# TSOC_ESP32S.net
KiCad netlist of a schematic drawn in EAGLE
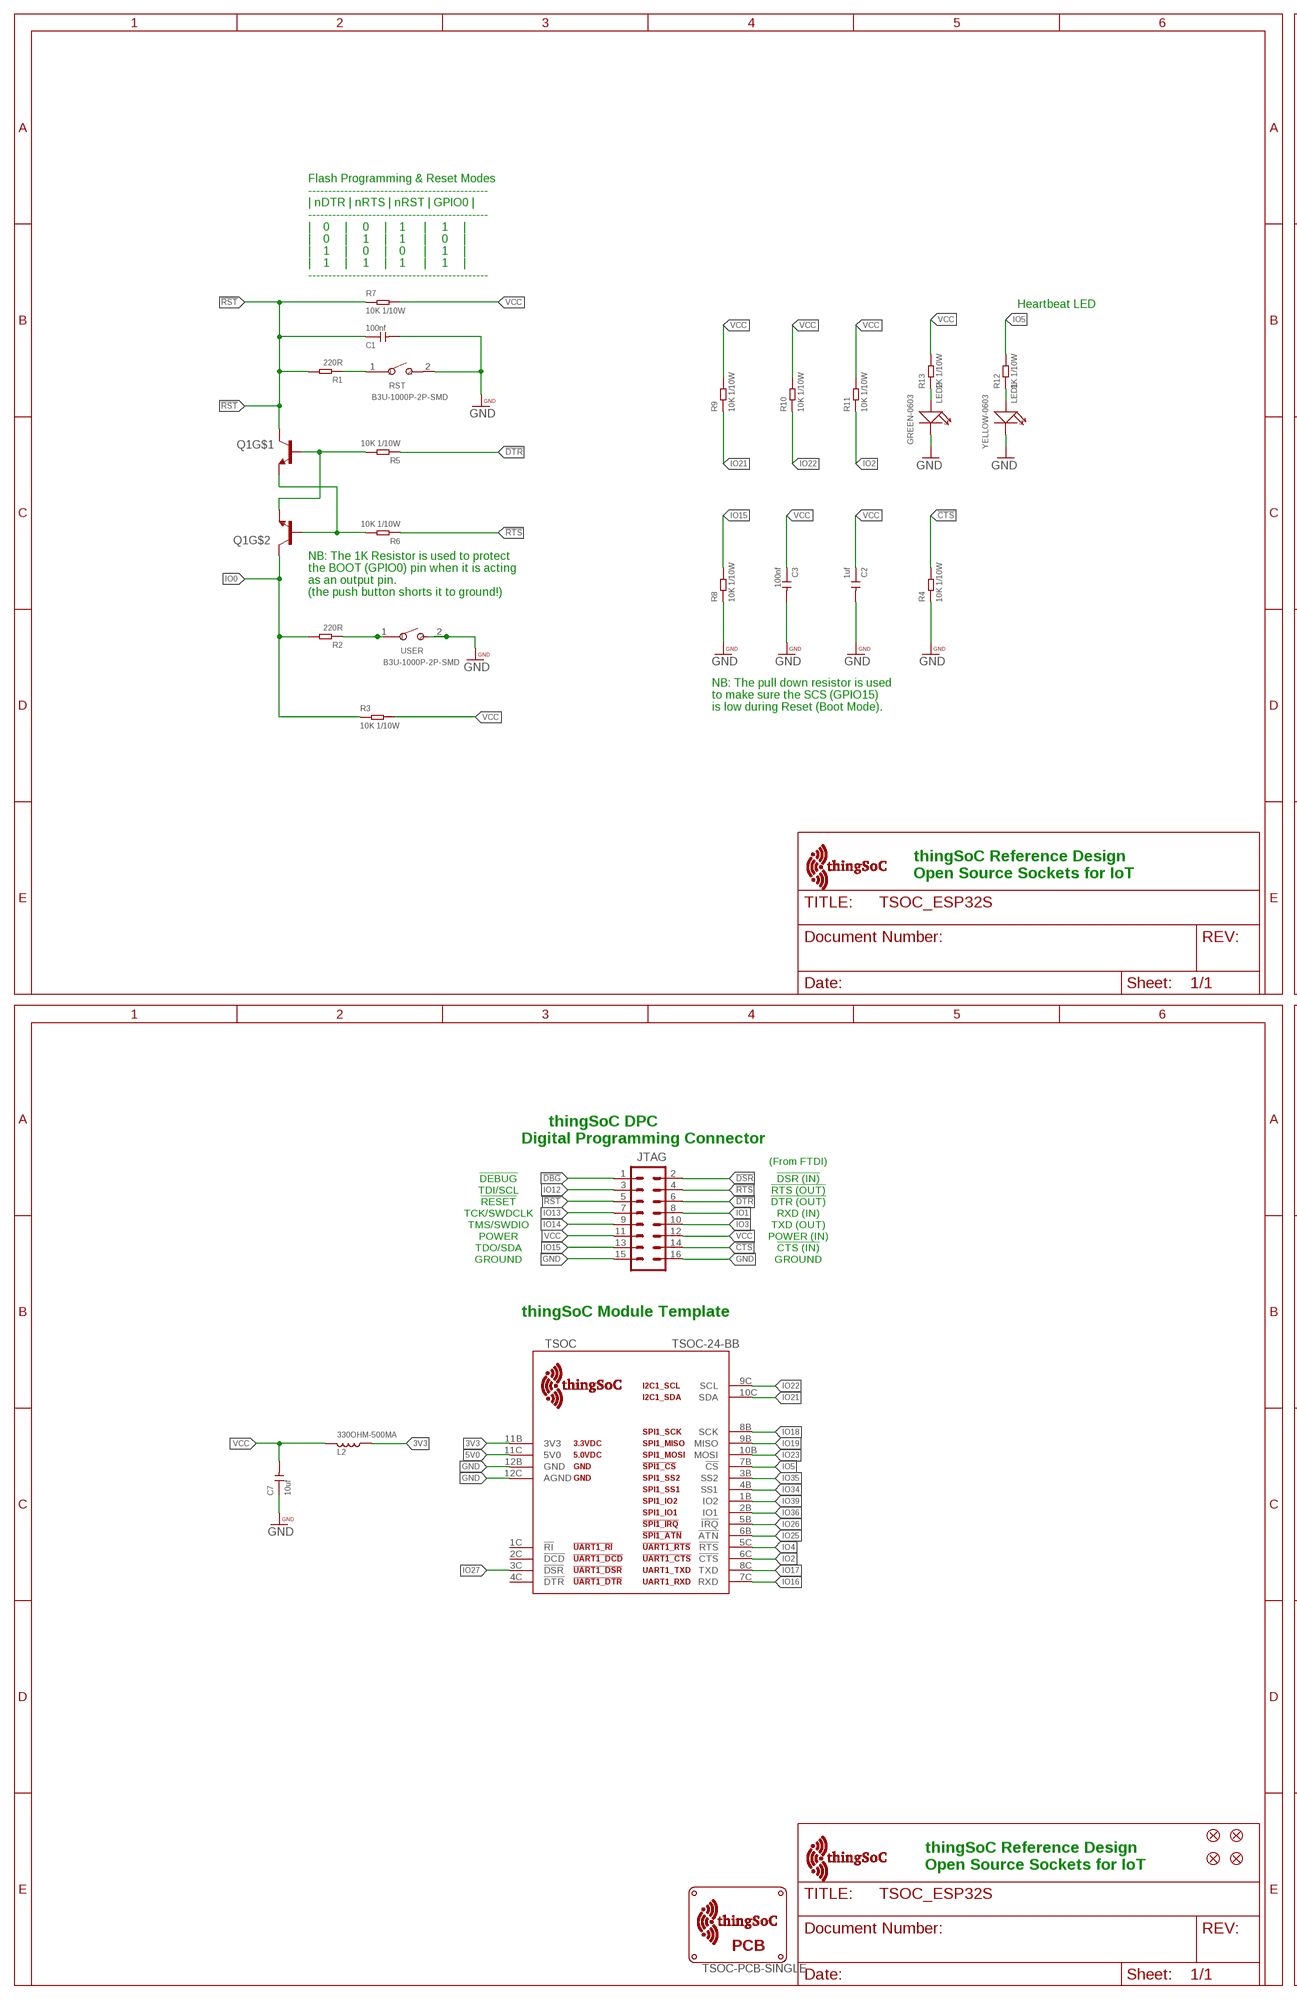
[diagram p0: schematic, sheet 1, part 1 of 2]
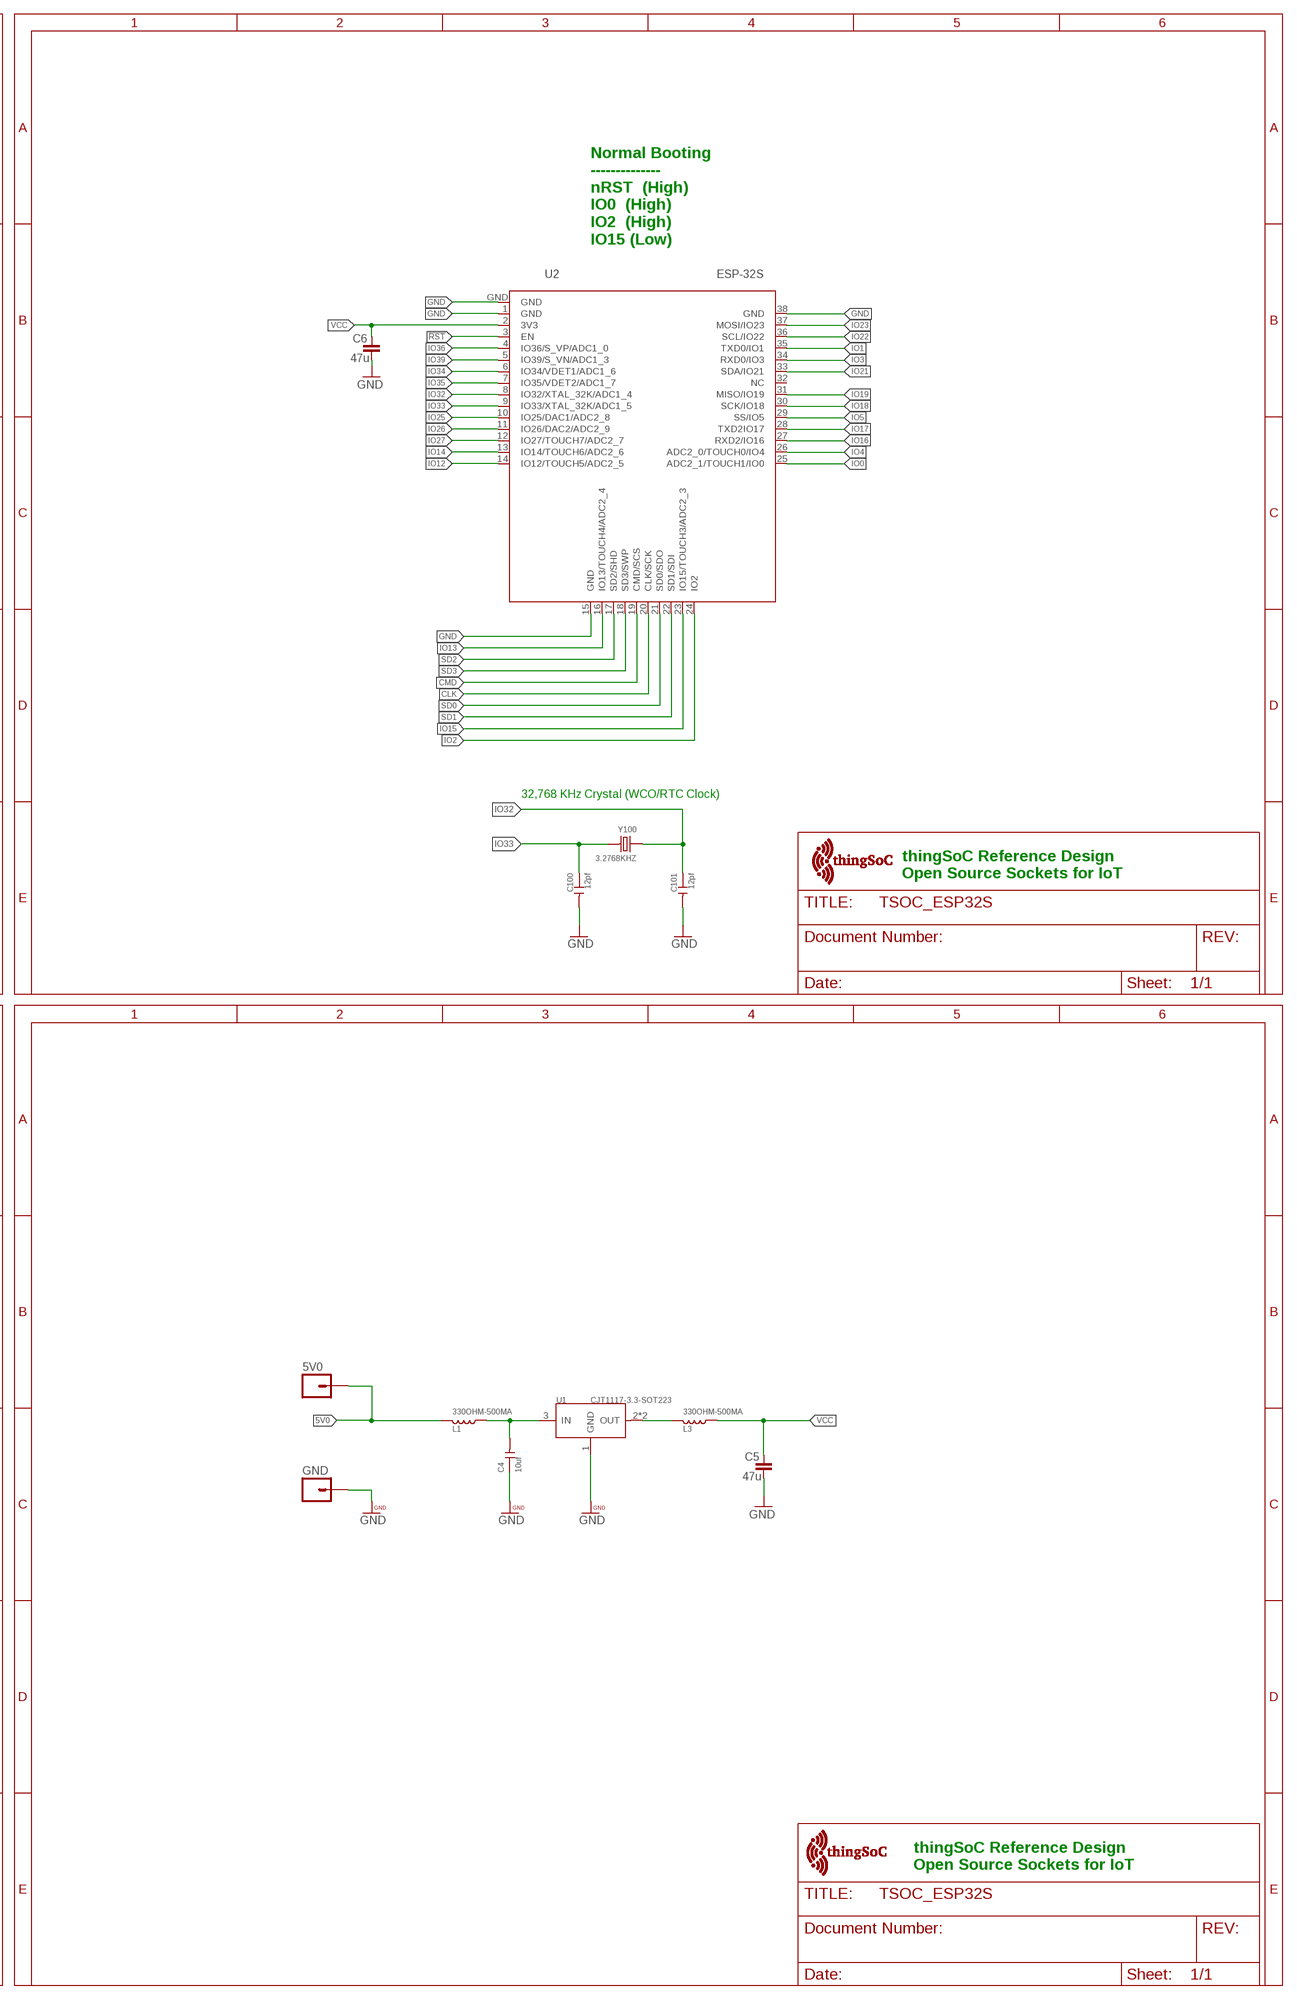
[diagram p1: schematic, sheet 1, part 2 of 2]

(export (version "E")
  (design (tool "Eeschema 10.0.6"))
  (components
    (comp (ref "$$U$1")
      (value "TSOC-LOGO-SMALL")
      (footprint "eagle-import:TSOC-LOGO-SML")
      (libsource (lib "eagle-import") (part "TSOC-LOGO-SMALL"))
    )
    (comp (ref "$$U$2")
      (value "TSOC-LOGO-SMALL")
      (footprint "eagle-import:TSOC-LOGO-SML")
      (libsource (lib "eagle-import") (part "TSOC-LOGO-SMALL"))
    )
    (comp (ref "5V0")
      (value "M01PTH")
      (footprint "eagle-import:1X01")
      (libsource (lib "eagle-import") (part "M01PTH"))
    )
    (comp (ref "C1")
      (value "100nf")
      (footprint "eagle-import:C0603")
      (fields (field (name "MPN") "CC0603KRX7R9BB104"))
      (libsource (lib "eagle-import") (part "CERAMIC-100NF-50V-10%-X7R(0603)"))
    )
    (comp (ref "C2")
      (value "1uf")
      (footprint "eagle-import:C0603")
      (fields (field (name "MPN") "CC0603KRX7R8BB105"))
      (libsource (lib "eagle-import") (part "CERAMIC-1UF-25V-10%-X7R(0603)"))
    )
    (comp (ref "C3")
      (value "100nf")
      (footprint "eagle-import:C0603")
      (fields (field (name "MPN") "CC0603KRX7R9BB104"))
      (libsource (lib "eagle-import") (part "CERAMIC-100NF-50V-10%-X7R(0603)"))
    )
    (comp (ref "C4")
      (value "10uf")
      (footprint "eagle-import:C0603")
      (fields (field (name "MPN") "CC0603KRX5R6BB106"))
      (libsource (lib "eagle-import") (part "CERAMIC-10UF-10V-10%-X5R(0603)"))
    )
    (comp (ref "C5")
      (value "47u")
      (footprint "eagle-import:C1206")
      (libsource (lib "eagle-import") (part "CAPACITOR-1206"))
    )
    (comp (ref "C6")
      (value "47u")
      (footprint "eagle-import:C1206")
      (libsource (lib "eagle-import") (part "CAPACITOR-1206"))
    )
    (comp (ref "C7")
      (value "10uf")
      (footprint "eagle-import:C0603")
      (fields (field (name "MPN") "CC0603KRX5R6BB106"))
      (libsource (lib "eagle-import") (part "CERAMIC-10UF-10V-10%-X5R(0603)"))
    )
    (comp (ref "C100")
      (value "12pf")
      (footprint "eagle-import:C0603")
      (fields (field (name "MPN") "CC0603JRNPO9BN120"))
      (libsource (lib "eagle-import") (part "CERAMIC-12PF-50V-5%-NPO(0603)"))
    )
    (comp (ref "C101")
      (value "12pf")
      (footprint "eagle-import:C0603")
      (fields (field (name "MPN") "CC0603JRNPO9BN120"))
      (libsource (lib "eagle-import") (part "CERAMIC-12PF-50V-5%-NPO(0603)"))
    )
    (comp (ref "FID1")
      (value "FIDUCIALUFIDUCIAL")
      (footprint "eagle-import:MICRO-FIDUCIAL")
      (libsource (lib "eagle-import") (part "FIDUCIALUFIDUCIAL"))
    )
    (comp (ref "FID2")
      (value "FIDUCIALUFIDUCIAL")
      (footprint "eagle-import:MICRO-FIDUCIAL")
      (libsource (lib "eagle-import") (part "FIDUCIALUFIDUCIAL"))
    )
    (comp (ref "FID3")
      (value "FIDUCIALUFIDUCIAL")
      (footprint "eagle-import:MICRO-FIDUCIAL")
      (libsource (lib "eagle-import") (part "FIDUCIALUFIDUCIAL"))
    )
    (comp (ref "FID4")
      (value "FIDUCIALUFIDUCIAL")
      (footprint "eagle-import:MICRO-FIDUCIAL")
      (libsource (lib "eagle-import") (part "FIDUCIALUFIDUCIAL"))
    )
    (comp (ref "GND")
      (value "M01PTH")
      (footprint "eagle-import:1X01")
      (libsource (lib "eagle-import") (part "M01PTH"))
    )
    (comp (ref "JTAG")
      (value "M08X2")
      (footprint "eagle-import:2X8")
      (libsource (lib "eagle-import") (part "M08X2"))
    )
    (comp (ref "L1")
      (value "330OHM-500MA")
      (footprint "eagle-import:L0603")
      (fields (field (name "MPN") "BLM18AG121SN1D"))
      (libsource (lib "eagle-import") (part "SMD-FERRITE-CHIP-120-OHM-500MA(0603)"))
    )
    (comp (ref "L2")
      (value "330OHM-500MA")
      (footprint "eagle-import:L0603")
      (fields (field (name "MPN") "BLM18AG121SN1D"))
      (libsource (lib "eagle-import") (part "SMD-FERRITE-CHIP-120-OHM-500MA(0603)"))
    )
    (comp (ref "L3")
      (value "330OHM-500MA")
      (footprint "eagle-import:L0603")
      (fields (field (name "MPN") "BLM18AG121SN1D"))
      (libsource (lib "eagle-import") (part "SMD-FERRITE-CHIP-120-OHM-500MA(0603)"))
    )
    (comp (ref "LED1")
      (value "YELLOW-0603")
      (footprint "eagle-import:LED-0603")
      (fields (field (name "MPN") "19-217-Y5C-AM1N1VY-3T"))
      (libsource (lib "eagle-import") (part "SMD-LED-CLEAR-YELLOW(0603)"))
    )
    (comp (ref "LED2")
      (value "GREEN-0603")
      (footprint "eagle-import:LED-0603")
      (fields (field (name "MPN") "19-217-G7C-AN1P2-3T"))
      (libsource (lib "eagle-import") (part "SMD-LED-CLEAR-GREEN(0603)"))
    )
    (comp (ref "Q1")
      (value "MMBT2222A")
      (footprint "eagle-import:SOT363")
      (libsource (lib "eagle-import") (part "MMDT3904"))
    )
    (comp (ref "R1")
      (value "220R")
      (footprint "eagle-import:R0603")
      (fields (field (name "MPN") "RC0603JR-07220RL"))
      (libsource (lib "eagle-import") (part "SMD-RES-220R-5%-1/10W(0603)"))
    )
    (comp (ref "R2")
      (value "220R")
      (footprint "eagle-import:R0603")
      (fields (field (name "MPN") "RC0603JR-07220RL"))
      (libsource (lib "eagle-import") (part "SMD-RES-220R-5%-1/10W(0603)"))
    )
    (comp (ref "R3")
      (value "10K 1/10W")
      (footprint "eagle-import:R0603")
      (fields (field (name "MPN") "RC0603JR-0710KL"))
      (libsource (lib "eagle-import") (part "SMD-RES-10K-5%-1/10W(0603)"))
    )
    (comp (ref "R4")
      (value "10K 1/10W")
      (footprint "eagle-import:R0603")
      (fields (field (name "MPN") "RC0603JR-0710KL"))
      (libsource (lib "eagle-import") (part "SMD-RES-10K-5%-1/10W(0603)"))
    )
    (comp (ref "R5")
      (value "10K 1/10W")
      (footprint "eagle-import:R0603")
      (fields (field (name "MPN") "RC0603JR-0710KL"))
      (libsource (lib "eagle-import") (part "SMD-RES-10K-5%-1/10W(0603)"))
    )
    (comp (ref "R6")
      (value "10K 1/10W")
      (footprint "eagle-import:R0603")
      (fields (field (name "MPN") "RC0603JR-0710KL"))
      (libsource (lib "eagle-import") (part "SMD-RES-10K-5%-1/10W(0603)"))
    )
    (comp (ref "R7")
      (value "10K 1/10W")
      (footprint "eagle-import:R0603")
      (fields (field (name "MPN") "RC0603JR-0710KL"))
      (libsource (lib "eagle-import") (part "SMD-RES-10K-5%-1/10W(0603)"))
    )
    (comp (ref "R8")
      (value "10K 1/10W")
      (footprint "eagle-import:R0603")
      (fields (field (name "MPN") "RC0603JR-0710KL"))
      (libsource (lib "eagle-import") (part "SMD-RES-10K-5%-1/10W(0603)"))
    )
    (comp (ref "R9")
      (value "10K 1/10W")
      (footprint "eagle-import:R0603")
      (fields (field (name "MPN") "RC0603JR-0710KL"))
      (libsource (lib "eagle-import") (part "SMD-RES-10K-5%-1/10W(0603)"))
    )
    (comp (ref "R10")
      (value "10K 1/10W")
      (footprint "eagle-import:R0603")
      (fields (field (name "MPN") "RC0603JR-0710KL"))
      (libsource (lib "eagle-import") (part "SMD-RES-10K-5%-1/10W(0603)"))
    )
    (comp (ref "R11")
      (value "10K 1/10W")
      (footprint "eagle-import:R0603")
      (fields (field (name "MPN") "RC0603JR-0710KL"))
      (libsource (lib "eagle-import") (part "SMD-RES-10K-5%-1/10W(0603)"))
    )
    (comp (ref "R12")
      (value "1K 1/10W")
      (footprint "eagle-import:R0603")
      (fields (field (name "MPN") "RC0603JR-071KL"))
      (libsource (lib "eagle-import") (part "SMD-RES-1K-5%-1/10W(0603)"))
    )
    (comp (ref "R13")
      (value "1K 1/10W")
      (footprint "eagle-import:R0603")
      (fields (field (name "MPN") "RC0603JR-071KL"))
      (libsource (lib "eagle-import") (part "SMD-RES-1K-5%-1/10W(0603)"))
    )
    (comp (ref "RST")
      (value "B3U-1000P-2P-SMD")
      (footprint "eagle-import:SW2-2.6-3.0X2.5X1.2+0.4MM")
      (libsource (lib "eagle-import") (part "SMD-BUTTON(2P-3.0X2.5X1.2+0.4MM)-B3U-1000P-2P-SMD"))
    )
    (comp (ref "TSOC")
      (value "TSOC-24-BB")
      (footprint "eagle-import:TSOC-BB-S24")
      (libsource (lib "eagle-import") (part "TSOC-24-BB"))
    )
    (comp (ref "U$1")
      (value "TSOC-PCB-SINGLE")
      (footprint "eagle-import:TSOC-BB-BRD-DIM")
      (libsource (lib "eagle-import") (part "TSOC-PCB-SINGLE"))
    )
    (comp (ref "U$101")
      (value "TSOC-LOGO-SMALL")
      (footprint "eagle-import:TSOC-LOGO-SML")
      (libsource (lib "eagle-import") (part "TSOC-LOGO-SMALL"))
    )
    (comp (ref "U$102")
      (value "TSOC-LOGO-LRG")
      (footprint "eagle-import:TSOC-LOGO-LRG")
      (libsource (lib "eagle-import") (part "TSOC-LOGO-LRG"))
    )
    (comp (ref "U1")
      (value "CJT1117-3.3-SOT223")
      (footprint "eagle-import:SOT-223")
      (fields (field (name "MPN") "CJT1117-3.3"))
      (libsource (lib "eagle-import") (part "PMIC-CJT1117-3.3(SOT223)"))
    )
    (comp (ref "U2")
      (value "ESP-32S")
      (footprint "eagle-import:ESP-32S")
      (libsource (lib "eagle-import") (part "ESP-32S"))
    )
    (comp (ref "USER")
      (value "B3U-1000P-2P-SMD")
      (footprint "eagle-import:SW2-2.6-3.0X2.5X1.2+0.4MM")
      (libsource (lib "eagle-import") (part "SMD-BUTTON(2P-3.0X2.5X1.2+0.4MM)-B3U-1000P-2P-SMD"))
    )
    (comp (ref "Y100")
      (value "3.2768KHZ")
      (footprint "eagle-import:X2-SMD-L2.0X1.2X0.55MM")
      (fields (field (name "MPN") "FC-12M"))
      (libsource (lib "eagle-import") (part "SMD-CRYSTAL-32.768KHZ-12.5PF-20PPM-90K(2P-L2.0X1.2MM)"))
    )
  )
  (nets
    (net (code "1") (name "/~{CTS}") (class "Default")
      (node (ref "JTAG") (pin "14") (pinfunction "14_14") (pintype "passive"))
      (node (ref "R4") (pin "2") (pinfunction "2_2") (pintype "passive"))
    )
    (net (code "2") (name "/~{DBG}") (class "Default")
      (node (ref "JTAG") (pin "1") (pinfunction "1_1") (pintype "passive"))
    )
    (net (code "3") (name "/~{DSR}") (class "Default")
      (node (ref "JTAG") (pin "2") (pinfunction "2_2") (pintype "passive"))
    )
    (net (code "4") (name "/~{DTR}") (class "Default")
      (node (ref "JTAG") (pin "6") (pinfunction "6_6") (pintype "passive"))
      (node (ref "R5") (pin "1") (pinfunction "1_1") (pintype "passive"))
    )
    (net (code "5") (name "/~{RST}") (class "Default")
      (node (ref "C1") (pin "1") (pinfunction "1_1") (pintype "passive"))
      (node (ref "JTAG") (pin "5") (pinfunction "5_5") (pintype "passive"))
      (node (ref "Q1") (pin "3") (pinfunction "C_3") (pintype "passive"))
      (node (ref "R1") (pin "2") (pinfunction "2_2") (pintype "passive"))
      (node (ref "R7") (pin "1") (pinfunction "1_1") (pintype "passive"))
      (node (ref "U2") (pin "3") (pinfunction "EN_3") (pintype "bidirectional"))
    )
    (net (code "6") (name "/~{RTS}") (class "Default")
      (node (ref "JTAG") (pin "4") (pinfunction "4_4") (pintype "passive"))
      (node (ref "R6") (pin "1") (pinfunction "1_1") (pintype "passive"))
    )
    (net (code "7") (name "3V3") (class "Default")
      (node (ref "L2") (pin "2") (pinfunction "2_2") (pintype "passive"))
      (node (ref "TSOC") (pin "11B") (pinfunction "3V3_11B") (pintype "bidirectional"))
    )
    (net (code "8") (name "5V0") (class "Default")
      (node (ref "5V0") (pin "1") (pinfunction "1_1") (pintype "passive"))
      (node (ref "L1") (pin "1") (pinfunction "1_1") (pintype "passive"))
      (node (ref "TSOC") (pin "11C") (pinfunction "5V0_11C") (pintype "bidirectional"))
    )
    (net (code "9") (name "CLK") (class "Default")
      (node (ref "U2") (pin "20") (pinfunction "CLK/SCK_20") (pintype "bidirectional"))
    )
    (net (code "10") (name "CMD") (class "Default")
      (node (ref "U2") (pin "19") (pinfunction "CMD/SCS_19") (pintype "bidirectional"))
    )
    (net (code "11") (name "GND") (class "Default")
      (node (ref "C1") (pin "2") (pinfunction "2_2") (pintype "passive"))
      (node (ref "C100") (pin "2") (pinfunction "2_2") (pintype "passive"))
      (node (ref "C101") (pin "2") (pinfunction "2_2") (pintype "passive"))
      (node (ref "C2") (pin "2") (pinfunction "2_2") (pintype "passive"))
      (node (ref "C3") (pin "2") (pinfunction "2_2") (pintype "passive"))
      (node (ref "C4") (pin "1") (pinfunction "1_1") (pintype "passive"))
      (node (ref "C5") (pin "1") (pinfunction "1_1") (pintype "passive"))
      (node (ref "C6") (pin "1") (pinfunction "1_1") (pintype "passive"))
      (node (ref "C7") (pin "1") (pinfunction "1_1") (pintype "passive"))
      (node (ref "GND") (pin "1") (pinfunction "1_1") (pintype "passive"))
      (node (ref "JTAG") (pin "15") (pinfunction "15_15") (pintype "passive"))
      (node (ref "JTAG") (pin "16") (pinfunction "16_16") (pintype "passive"))
      (node (ref "LED1") (pin "-") (pinfunction "-_-") (pintype "passive"))
      (node (ref "LED2") (pin "-") (pinfunction "-_-") (pintype "passive"))
      (node (ref "R4") (pin "1") (pinfunction "1_1") (pintype "passive"))
      (node (ref "R8") (pin "1") (pinfunction "1_1") (pintype "passive"))
      (node (ref "RST") (pin "2") (pinfunction "2_2") (pintype "bidirectional"))
      (node (ref "TSOC") (pin "12B") (pinfunction "GND_12B") (pintype "bidirectional"))
      (node (ref "TSOC") (pin "12C") (pinfunction "AGND_12C") (pintype "bidirectional"))
      (node (ref "U1") (pin "1") (pinfunction "GND_1") (pintype "bidirectional"))
      (node (ref "U2") (pin "1") (pinfunction "GND_1") (pintype "bidirectional"))
      (node (ref "U2") (pin "15") (pinfunction "GND_15") (pintype "bidirectional"))
      (node (ref "U2") (pin "38") (pinfunction "GND_38") (pintype "bidirectional"))
      (node (ref "U2") (pin "GND") (pinfunction "GND_GND") (pintype "bidirectional"))
      (node (ref "USER") (pin "2") (pinfunction "2_2") (pintype "bidirectional"))
    )
    (net (code "12") (name "IO0") (class "Default")
      (node (ref "Q1") (pin "6") (pinfunction "C_6") (pintype "passive"))
      (node (ref "R2") (pin "2") (pinfunction "2_2") (pintype "passive"))
      (node (ref "R3") (pin "1") (pinfunction "1_1") (pintype "passive"))
      (node (ref "U2") (pin "25") (pinfunction "ADC2_1/TOUCH1/IO0_25") (pintype "bidirectional"))
    )
    (net (code "13") (name "IO1") (class "Default")
      (node (ref "JTAG") (pin "8") (pinfunction "8_8") (pintype "passive"))
      (node (ref "U2") (pin "35") (pinfunction "TXD0/IO1_35") (pintype "bidirectional"))
    )
    (net (code "14") (name "IO2") (class "Default")
      (node (ref "R11") (pin "1") (pinfunction "1_1") (pintype "passive"))
      (node (ref "TSOC") (pin "6C") (pinfunction "~{CTS}_6C") (pintype "bidirectional"))
      (node (ref "U2") (pin "24") (pinfunction "IO2_24") (pintype "bidirectional"))
    )
    (net (code "15") (name "IO3") (class "Default")
      (node (ref "JTAG") (pin "10") (pinfunction "10_10") (pintype "passive"))
      (node (ref "U2") (pin "34") (pinfunction "RXD0/IO3_34") (pintype "bidirectional"))
    )
    (net (code "16") (name "IO4") (class "Default")
      (node (ref "TSOC") (pin "5C") (pinfunction "~{RTS}_5C") (pintype "bidirectional"))
      (node (ref "U2") (pin "26") (pinfunction "ADC2_0/TOUCH0/IO4_26") (pintype "bidirectional"))
    )
    (net (code "17") (name "IO5") (class "Default")
      (node (ref "R12") (pin "2") (pinfunction "2_2") (pintype "passive"))
      (node (ref "TSOC") (pin "7B") (pinfunction "~{CS}_7B") (pintype "bidirectional"))
      (node (ref "U2") (pin "29") (pinfunction "SS/IO5_29") (pintype "bidirectional"))
    )
    (net (code "18") (name "IO12") (class "Default")
      (node (ref "JTAG") (pin "3") (pinfunction "3_3") (pintype "passive"))
      (node (ref "U2") (pin "14") (pinfunction "IO12/TOUCH5/ADC2_5_14") (pintype "bidirectional"))
    )
    (net (code "19") (name "IO13") (class "Default")
      (node (ref "JTAG") (pin "7") (pinfunction "7_7") (pintype "passive"))
      (node (ref "U2") (pin "16") (pinfunction "IO13/TOUCH4/ADC2_4_16") (pintype "bidirectional"))
    )
    (net (code "20") (name "IO14") (class "Default")
      (node (ref "JTAG") (pin "9") (pinfunction "9_9") (pintype "passive"))
      (node (ref "U2") (pin "13") (pinfunction "IO14/TOUCH6/ADC2_6_13") (pintype "bidirectional"))
    )
    (net (code "21") (name "IO15") (class "Default")
      (node (ref "JTAG") (pin "13") (pinfunction "13_13") (pintype "passive"))
      (node (ref "R8") (pin "2") (pinfunction "2_2") (pintype "passive"))
      (node (ref "U2") (pin "23") (pinfunction "IO15/TOUCH3/ADC2_3_23") (pintype "bidirectional"))
    )
    (net (code "22") (name "IO16") (class "Default")
      (node (ref "TSOC") (pin "7C") (pinfunction "RXD_7C") (pintype "bidirectional"))
      (node (ref "U2") (pin "27") (pinfunction "RXD2/IO16_27") (pintype "bidirectional"))
    )
    (net (code "23") (name "IO17") (class "Default")
      (node (ref "TSOC") (pin "8C") (pinfunction "TXD_8C") (pintype "bidirectional"))
      (node (ref "U2") (pin "28") (pinfunction "TXD2IO17_28") (pintype "bidirectional"))
    )
    (net (code "24") (name "IO18") (class "Default")
      (node (ref "TSOC") (pin "8B") (pinfunction "SCK_8B") (pintype "bidirectional"))
      (node (ref "U2") (pin "30") (pinfunction "SCK/IO18_30") (pintype "bidirectional"))
    )
    (net (code "25") (name "IO19") (class "Default")
      (node (ref "TSOC") (pin "9B") (pinfunction "MISO_9B") (pintype "bidirectional"))
      (node (ref "U2") (pin "31") (pinfunction "MISO/IO19_31") (pintype "bidirectional"))
    )
    (net (code "26") (name "IO21") (class "Default")
      (node (ref "R9") (pin "1") (pinfunction "1_1") (pintype "passive"))
      (node (ref "TSOC") (pin "10C") (pinfunction "SDA_10C") (pintype "bidirectional"))
      (node (ref "U2") (pin "33") (pinfunction "SDA/IO21_33") (pintype "bidirectional"))
    )
    (net (code "27") (name "IO22") (class "Default")
      (node (ref "R10") (pin "1") (pinfunction "1_1") (pintype "passive"))
      (node (ref "TSOC") (pin "9C") (pinfunction "SCL_9C") (pintype "bidirectional"))
      (node (ref "U2") (pin "36") (pinfunction "SCL/IO22_36") (pintype "bidirectional"))
    )
    (net (code "28") (name "IO23") (class "Default")
      (node (ref "TSOC") (pin "10B") (pinfunction "MOSI_10B") (pintype "bidirectional"))
      (node (ref "U2") (pin "37") (pinfunction "MOSI/IO23_37") (pintype "bidirectional"))
    )
    (net (code "29") (name "IO25") (class "Default")
      (node (ref "TSOC") (pin "6B") (pinfunction "~{ATN}_6B") (pintype "bidirectional"))
      (node (ref "U2") (pin "10") (pinfunction "IO25/DAC1/ADC2_8_10") (pintype "bidirectional"))
    )
    (net (code "30") (name "IO26") (class "Default")
      (node (ref "TSOC") (pin "5B") (pinfunction "~{IRQ}_5B") (pintype "bidirectional"))
      (node (ref "U2") (pin "11") (pinfunction "IO26/DAC2/ADC2_9_11") (pintype "bidirectional"))
    )
    (net (code "31") (name "IO27") (class "Default")
      (node (ref "TSOC") (pin "3C") (pinfunction "~{DSR}_3C") (pintype "bidirectional"))
      (node (ref "U2") (pin "12") (pinfunction "IO27/TOUCH7/ADC2_7_12") (pintype "bidirectional"))
    )
    (net (code "32") (name "IO32") (class "Default")
      (node (ref "C101") (pin "1") (pinfunction "1_1") (pintype "passive"))
      (node (ref "U2") (pin "8") (pinfunction "IO32/XTAL_32K/ADC1_4_8") (pintype "bidirectional"))
      (node (ref "Y100") (pin "1") (pinfunction "1_1") (pintype "passive"))
    )
    (net (code "33") (name "IO33") (class "Default")
      (node (ref "C100") (pin "1") (pinfunction "1_1") (pintype "passive"))
      (node (ref "U2") (pin "9") (pinfunction "IO33/XTAL_32K/ADC1_5_9") (pintype "bidirectional"))
      (node (ref "Y100") (pin "2") (pinfunction "2_2") (pintype "passive"))
    )
    (net (code "34") (name "IO34") (class "Default")
      (node (ref "TSOC") (pin "4B") (pinfunction "SS1_4B") (pintype "bidirectional"))
      (node (ref "U2") (pin "6") (pinfunction "IO34/VDET1/ADC1_6_6") (pintype "bidirectional"))
    )
    (net (code "35") (name "IO35") (class "Default")
      (node (ref "TSOC") (pin "3B") (pinfunction "SS2_3B") (pintype "bidirectional"))
      (node (ref "U2") (pin "7") (pinfunction "IO35/VDET2/ADC1_7_7") (pintype "bidirectional"))
    )
    (net (code "36") (name "IO36") (class "Default")
      (node (ref "TSOC") (pin "2B") (pinfunction "IO1_2B") (pintype "bidirectional"))
      (node (ref "U2") (pin "4") (pinfunction "IO36/S_VP/ADC1_0_4") (pintype "bidirectional"))
    )
    (net (code "37") (name "IO39") (class "Default")
      (node (ref "TSOC") (pin "1B") (pinfunction "IO2_1B") (pintype "bidirectional"))
      (node (ref "U2") (pin "5") (pinfunction "IO39/S_VN/ADC1_3_5") (pintype "bidirectional"))
    )
    (net (code "38") (name "Net-(L3-Pad1)") (class "Default")
      (node (ref "L3") (pin "1") (pinfunction "1_1") (pintype "passive"))
      (node (ref "U1") (pin "2") (pinfunction "OUT_2") (pintype "bidirectional"))
      (node (ref "U1") (pin "TER") (pinfunction "OUT_TER") (pintype "bidirectional"))
    )
    (net (code "39") (name "Net-(LED1-Pad+)") (class "Default")
      (node (ref "LED1") (pin "+") (pinfunction "+_+") (pintype "passive"))
      (node (ref "R12") (pin "1") (pinfunction "1_1") (pintype "passive"))
    )
    (net (code "40") (name "Net-(LED2-Pad+)") (class "Default")
      (node (ref "LED2") (pin "+") (pinfunction "+_+") (pintype "passive"))
      (node (ref "R13") (pin "1") (pinfunction "1_1") (pintype "passive"))
    )
    (net (code "41") (name "Net-(Q1A-B)") (class "Default")
      (node (ref "Q1") (pin "1") (pinfunction "E_1") (pintype "passive"))
      (node (ref "Q1") (pin "5") (pinfunction "B_5") (pintype "passive"))
      (node (ref "R5") (pin "2") (pinfunction "2_2") (pintype "passive"))
    )
    (net (code "42") (name "Net-(Q1A-E)") (class "Default")
      (node (ref "Q1") (pin "2") (pinfunction "B_2") (pintype "passive"))
      (node (ref "Q1") (pin "4") (pinfunction "E_4") (pintype "passive"))
      (node (ref "R6") (pin "2") (pinfunction "2_2") (pintype "passive"))
    )
    (net (code "43") (name "Net-(R1-Pad1)") (class "Default")
      (node (ref "R1") (pin "1") (pinfunction "1_1") (pintype "passive"))
      (node (ref "RST") (pin "1") (pinfunction "1_1") (pintype "bidirectional"))
    )
    (net (code "44") (name "Net-(R2-Pad1)") (class "Default")
      (node (ref "R2") (pin "1") (pinfunction "1_1") (pintype "passive"))
      (node (ref "USER") (pin "1") (pinfunction "1_1") (pintype "bidirectional"))
    )
    (net (code "45") (name "Net-(U1-IN)") (class "Default")
      (node (ref "C4") (pin "2") (pinfunction "2_2") (pintype "passive"))
      (node (ref "L1") (pin "2") (pinfunction "2_2") (pintype "passive"))
      (node (ref "U1") (pin "3") (pinfunction "IN_3") (pintype "bidirectional"))
    )
    (net (code "46") (name "SD0") (class "Default")
      (node (ref "U2") (pin "21") (pinfunction "SD0/SDO_21") (pintype "bidirectional"))
    )
    (net (code "47") (name "SD1") (class "Default")
      (node (ref "U2") (pin "22") (pinfunction "SD1/SDI_22") (pintype "bidirectional"))
    )
    (net (code "48") (name "SD2") (class "Default")
      (node (ref "U2") (pin "17") (pinfunction "SD2/SHD_17") (pintype "bidirectional"))
    )
    (net (code "49") (name "SD3") (class "Default")
      (node (ref "U2") (pin "18") (pinfunction "SD3/SWP_18") (pintype "bidirectional"))
    )
    (net (code "50") (name "VCC") (class "Default")
      (node (ref "C2") (pin "1") (pinfunction "1_1") (pintype "passive"))
      (node (ref "C3") (pin "1") (pinfunction "1_1") (pintype "passive"))
      (node (ref "C5") (pin "2") (pinfunction "2_2") (pintype "passive"))
      (node (ref "C6") (pin "2") (pinfunction "2_2") (pintype "passive"))
      (node (ref "C7") (pin "2") (pinfunction "2_2") (pintype "passive"))
      (node (ref "JTAG") (pin "11") (pinfunction "11_11") (pintype "passive"))
      (node (ref "JTAG") (pin "12") (pinfunction "12_12") (pintype "passive"))
      (node (ref "L2") (pin "1") (pinfunction "1_1") (pintype "passive"))
      (node (ref "L3") (pin "2") (pinfunction "2_2") (pintype "passive"))
      (node (ref "R10") (pin "2") (pinfunction "2_2") (pintype "passive"))
      (node (ref "R11") (pin "2") (pinfunction "2_2") (pintype "passive"))
      (node (ref "R13") (pin "2") (pinfunction "2_2") (pintype "passive"))
      (node (ref "R3") (pin "2") (pinfunction "2_2") (pintype "passive"))
      (node (ref "R7") (pin "2") (pinfunction "2_2") (pintype "passive"))
      (node (ref "R9") (pin "2") (pinfunction "2_2") (pintype "passive"))
      (node (ref "U2") (pin "2") (pinfunction "3V3_2") (pintype "bidirectional"))
    )
    (net (code "51") (name "unconnected-(TSOC-~{DCD}-Pad2C)") (class "Default")
      (node (ref "TSOC") (pin "2C") (pinfunction "~{DCD}_2C") (pintype "bidirectional"))
    )
    (net (code "52") (name "unconnected-(TSOC-~{DTR}-Pad4C)") (class "Default")
      (node (ref "TSOC") (pin "4C") (pinfunction "~{DTR}_4C") (pintype "bidirectional"))
    )
    (net (code "53") (name "unconnected-(TSOC-~{RI}-Pad1C)") (class "Default")
      (node (ref "TSOC") (pin "1C") (pinfunction "~{RI}_1C") (pintype "bidirectional"))
    )
    (net (code "54") (name "unconnected-(U2-NC-Pad32)") (class "Default")
      (node (ref "U2") (pin "32") (pinfunction "NC_32") (pintype "bidirectional"))
    )
  )
)
